# SeniorDesignPCB.net
KiCad netlist of a schematic drawn in Altium Designer
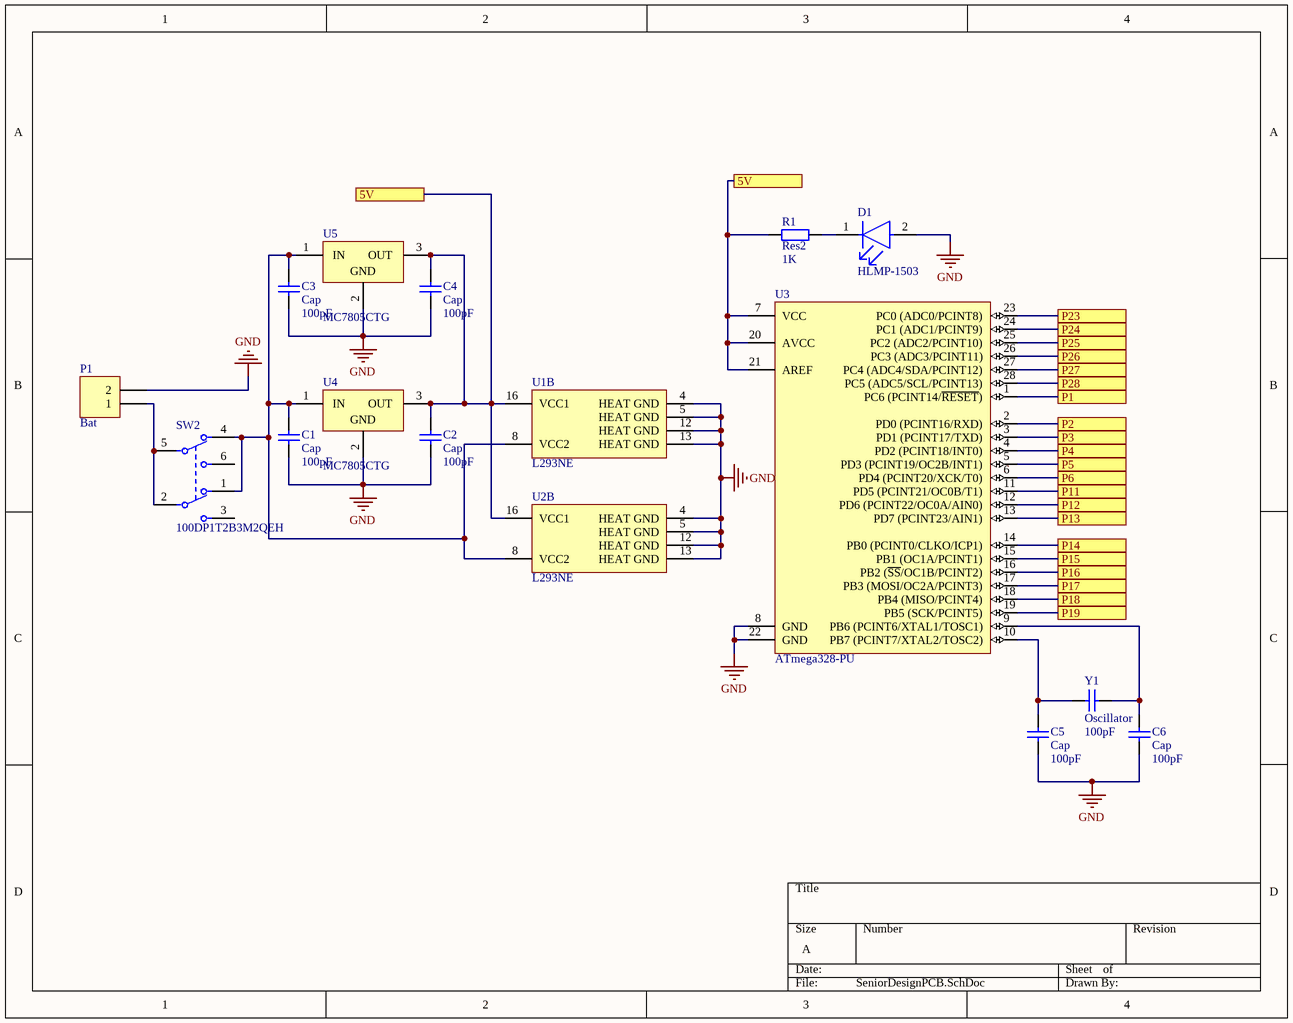
[diagram p0: SeniorDesignPCB.SchDoc]

(export (version "E")
  (design (tool "Eeschema 10.0.6"))
  (components
    (comp (ref "C1")
      (value "Cap")
      (footprint "RAD-0.3")
      (description "Capacitor 10 uF")
      (fields (field (name "ALTIUM_VALUE") "100pF") (field (name "PUBLISHER") "Altium Limited"))
      (libsource (lib "Miscellaneous Devices") (part "Cap"))
    )
    (comp (ref "C2")
      (value "Cap")
      (footprint "RAD-0.3")
      (description "Capacitor 10 uF")
      (fields (field (name "ALTIUM_VALUE") "100pF") (field (name "PUBLISHER") "Altium Limited"))
      (libsource (lib "Miscellaneous Devices") (part "Cap"))
    )
    (comp (ref "C3")
      (value "Cap")
      (footprint "RAD-0.3")
      (description "Capacitor 10 uF")
      (fields (field (name "ALTIUM_VALUE") "100pF") (field (name "PUBLISHER") "Altium Limited"))
      (libsource (lib "Miscellaneous Devices") (part "Cap"))
    )
    (comp (ref "C4")
      (value "Cap")
      (footprint "RAD-0.3")
      (description "Capacitor 10 uF")
      (fields (field (name "ALTIUM_VALUE") "100pF") (field (name "PUBLISHER") "Altium Limited"))
      (libsource (lib "Miscellaneous Devices") (part "Cap"))
    )
    (comp (ref "C5")
      (value "Cap")
      (footprint "RAD-0.3")
      (description "Capacitor 22 pF")
      (fields (field (name "ALTIUM_VALUE") "100pF") (field (name "PUBLISHER") "Altium Limited"))
      (libsource (lib "Miscellaneous Devices") (part "Cap"))
    )
    (comp (ref "C6")
      (value "Cap")
      (footprint "RAD-0.3")
      (description "Capacitor 22 pF")
      (fields (field (name "ALTIUM_VALUE") "100pF") (field (name "PUBLISHER") "Altium Limited"))
      (libsource (lib "Miscellaneous Devices") (part "Cap"))
    )
    (comp (ref "D1")
      (value "HLMP-1503")
      (footprint "FP-HLMP-1503-MFG")
      (description "LED GREEN DIFFUSED T-1 T/H")
      (fields
        (field (name "MANUFACTURER") "Broadcom")
        (field (name "OCTOPART") "https://octopart.com/hlmp-1503-broadcom-71130371")
      )
      (libsource (lib "Altium Content Vault") (part "8706943c75ba83719d021d2fdc84c58"))
    )
    (comp (ref "P1")
      (value "Bat")
      (footprint "HDR1X2")
      (description "Header, 2-Pin")
      (fields (field (name "PUBLISHER") "Altium Limited"))
      (libsource (lib "Miscellaneous Connectors") (part "Header 2"))
    )
    (comp (ref "R1")
      (value "Res2")
      (footprint "AXIAL-0.4")
      (description "Resistor 220 ohm")
      (fields (field (name "ALTIUM_VALUE") "1K") (field (name "PUBLISHER") "Altium Limited"))
      (libsource (lib "Miscellaneous Devices") (part "Res2"))
    )
    (comp (ref "SW2")
      (value "100DP1T2B3M2QEH")
      (footprint "FP-100DP1T2B3M2QEH-MFG")
      (description "DPDT Toggle Switch")
      (fields (field (name "MANUFACTURER") "E-Switch"))
      (libsource (lib "Altium Content Vault") (part "0cfc74b8a78428f8f812a73d8c28120"))
    )
    (comp (ref "U1")
      (value "L293NE")
      (footprint "NE0016A")
      (description "Quadruple Half-H Driver, 4.5 to 36 V, 0 to 70 degC, 16-Pin DIP, Pb-Free, Tube")
      (fields (field (name "MANUFACTURER") "Texas Instruments"))
      (libsource (lib "Altium Content Vault") (part "TI-L293-NE16"))
    )
    (comp (ref "U2")
      (value "L293NE")
      (footprint "NE0016A")
      (description "Quadruple Half-H Driver, 4.5 to 36 V, 0 to 70 degC, 16-Pin DIP, Pb-Free, Tube")
      (fields (field (name "MANUFACTURER") "Texas Instruments"))
      (libsource (lib "Altium Content Vault") (part "TI-L293-NE16"))
    )
    (comp (ref "U3")
      (value "ATmega328-PU")
      (footprint "28P3")
      (libsource (lib "Altium Content Vault") (part "MC-8B-ATM48-IL28"))
    )
    (comp (ref "U4")
      (value "MC7805CTG")
      (footprint "ONSC-TO-220-3-221AB-01")
      (description "Positive Voltage Regulator, 1 A, 5 V, 0 to 125 degC, 3-Pin TO-220, RoHS, Tube")
      (fields (field (name "MANUFACTURER") "ON Semiconductor"))
      (libsource (lib "Altium Content Vault") (part "ONSC-MC7805CTG-TO-220-3"))
    )
    (comp (ref "U5")
      (value "MC7805CTG")
      (footprint "ONSC-TO-220-3-221AB-01")
      (description "Positive Voltage Regulator, 1 A, 5 V, 0 to 125 degC, 3-Pin TO-220, RoHS, Tube")
      (fields (field (name "MANUFACTURER") "ON Semiconductor"))
      (libsource (lib "Altium Content Vault") (part "ONSC-MC7805CTG-TO-220-3"))
    )
    (comp (ref "Y1")
      (value "Oscillator")
      (footprint "RAD-0.3")
      (description "16 MHz oscillator")
      (fields (field (name "ALTIUM_VALUE") "100pF") (field (name "PUBLISHER") "Altium Limited"))
      (libsource (lib "Miscellaneous Devices") (part "Cap"))
    )
  )
  (nets
    (net (code "1") (name "/5V") (class "Default")
      (node (ref "C2") (pin "2") (pinfunction "2_2") (pintype "passive"))
      (node (ref "C4") (pin "2") (pinfunction "2_2") (pintype "passive"))
      (node (ref "R1") (pin "1") (pinfunction "1_1") (pintype "passive"))
      (node (ref "U1") (pin "16") (pinfunction "VCC1_16") (pintype "power_in"))
      (node (ref "U2") (pin "16") (pinfunction "VCC1_16") (pintype "power_in"))
      (node (ref "U3") (pin "20") (pinfunction "AVCC_20") (pintype "power_in"))
      (node (ref "U3") (pin "21") (pinfunction "AREF_21") (pintype "power_in"))
      (node (ref "U3") (pin "7") (pinfunction "VCC_7") (pintype "power_in"))
      (node (ref "U4") (pin "3") (pinfunction "OUT_3") (pintype "power_in"))
      (node (ref "U5") (pin "3") (pinfunction "OUT_3") (pintype "power_in"))
    )
    (net (code "2") (name "/P1") (class "Default")
      (node (ref "U3") (pin "1") (pinfunction "PC6_(PCINT14/~{RESET})_1") (pintype "bidirectional"))
    )
    (net (code "3") (name "/P2") (class "Default")
      (node (ref "U3") (pin "2") (pinfunction "PD0_(PCINT16/RXD)_2") (pintype "bidirectional"))
    )
    (net (code "4") (name "/P3") (class "Default")
      (node (ref "U3") (pin "3") (pinfunction "PD1_(PCINT17/TXD)_3") (pintype "bidirectional"))
    )
    (net (code "5") (name "/P4") (class "Default")
      (node (ref "U3") (pin "4") (pinfunction "PD2_(PCINT18/INT0)_4") (pintype "bidirectional"))
    )
    (net (code "6") (name "/P5") (class "Default")
      (node (ref "U3") (pin "5") (pinfunction "PD3_(PCINT19/OC2B/INT1)_5") (pintype "bidirectional"))
    )
    (net (code "7") (name "/P6") (class "Default")
      (node (ref "U3") (pin "6") (pinfunction "PD4_(PCINT20/XCK/T0)_6") (pintype "bidirectional"))
    )
    (net (code "8") (name "/P11") (class "Default")
      (node (ref "U3") (pin "11") (pinfunction "PD5_(PCINT21/OC0B/T1)_11") (pintype "bidirectional"))
    )
    (net (code "9") (name "/P12") (class "Default")
      (node (ref "U3") (pin "12") (pinfunction "PD6_(PCINT22/OC0A/AIN0)_12") (pintype "bidirectional"))
    )
    (net (code "10") (name "/P13") (class "Default")
      (node (ref "U3") (pin "13") (pinfunction "PD7_(PCINT23/AIN1)_13") (pintype "bidirectional"))
    )
    (net (code "11") (name "/P14") (class "Default")
      (node (ref "U3") (pin "14") (pinfunction "PB0_(PCINT0/CLKO/ICP1)_14") (pintype "bidirectional"))
    )
    (net (code "12") (name "/P15") (class "Default")
      (node (ref "U3") (pin "15") (pinfunction "PB1_(OC1A/PCINT1)_15") (pintype "bidirectional"))
    )
    (net (code "13") (name "/P16") (class "Default")
      (node (ref "U3") (pin "16") (pinfunction "PB2_(~{SS}/OC1B/PCINT2)_16") (pintype "bidirectional"))
    )
    (net (code "14") (name "/P17") (class "Default")
      (node (ref "U3") (pin "17") (pinfunction "PB3_(MOSI/OC2A/PCINT3)_17") (pintype "bidirectional"))
    )
    (net (code "15") (name "/P18") (class "Default")
      (node (ref "U3") (pin "18") (pinfunction "PB4_(MISO/PCINT4)_18") (pintype "bidirectional"))
    )
    (net (code "16") (name "/P19") (class "Default")
      (node (ref "U3") (pin "19") (pinfunction "PB5_(SCK/PCINT5)_19") (pintype "bidirectional"))
    )
    (net (code "17") (name "/P23") (class "Default")
      (node (ref "U3") (pin "23") (pinfunction "PC0_(ADC0/PCINT8)_23") (pintype "bidirectional"))
    )
    (net (code "18") (name "/P24") (class "Default")
      (node (ref "U3") (pin "24") (pinfunction "PC1_(ADC1/PCINT9)_24") (pintype "bidirectional"))
    )
    (net (code "19") (name "/P25") (class "Default")
      (node (ref "U3") (pin "25") (pinfunction "PC2_(ADC2/PCINT10)_25") (pintype "bidirectional"))
    )
    (net (code "20") (name "/P26") (class "Default")
      (node (ref "U3") (pin "26") (pinfunction "PC3_(ADC3/PCINT11)_26") (pintype "bidirectional"))
    )
    (net (code "21") (name "/P27") (class "Default")
      (node (ref "U3") (pin "27") (pinfunction "PC4_(ADC4/SDA/PCINT12)_27") (pintype "bidirectional"))
    )
    (net (code "22") (name "/P28") (class "Default")
      (node (ref "U3") (pin "28") (pinfunction "PC5_(ADC5/SCL/PCINT13)_28") (pintype "bidirectional"))
    )
    (net (code "23") (name "GND") (class "Default")
      (node (ref "C1") (pin "1") (pinfunction "1_1") (pintype "passive"))
      (node (ref "C2") (pin "1") (pinfunction "1_1") (pintype "passive"))
      (node (ref "C3") (pin "1") (pinfunction "1_1") (pintype "passive"))
      (node (ref "C4") (pin "1") (pinfunction "1_1") (pintype "passive"))
      (node (ref "C5") (pin "1") (pinfunction "1_1") (pintype "passive"))
      (node (ref "C6") (pin "1") (pinfunction "1_1") (pintype "passive"))
      (node (ref "D1") (pin "2") (pinfunction "A_2") (pintype "passive"))
      (node (ref "P1") (pin "2") (pinfunction "2_2") (pintype "passive"))
      (node (ref "U1") (pin "12") (pinfunction "HEAT_GND_12") (pintype "power_in"))
      (node (ref "U1") (pin "13") (pinfunction "HEAT_GND_13") (pintype "power_in"))
      (node (ref "U1") (pin "4") (pinfunction "HEAT_GND_4") (pintype "power_in"))
      (node (ref "U1") (pin "5") (pinfunction "HEAT_GND_5") (pintype "power_in"))
      (node (ref "U2") (pin "12") (pinfunction "HEAT_GND_12") (pintype "power_in"))
      (node (ref "U2") (pin "13") (pinfunction "HEAT_GND_13") (pintype "power_in"))
      (node (ref "U2") (pin "4") (pinfunction "HEAT_GND_4") (pintype "power_in"))
      (node (ref "U2") (pin "5") (pinfunction "HEAT_GND_5") (pintype "power_in"))
      (node (ref "U3") (pin "22") (pinfunction "GND_22") (pintype "power_in"))
      (node (ref "U3") (pin "8") (pinfunction "GND_8") (pintype "power_in"))
      (node (ref "U4") (pin "2") (pinfunction "GND_2") (pintype "power_in"))
      (node (ref "U5") (pin "2") (pinfunction "GND_2") (pintype "power_in"))
    )
    (net (code "24") (name "Net-(D1-C)") (class "Default")
      (node (ref "D1") (pin "1") (pinfunction "C_1") (pintype "passive"))
      (node (ref "R1") (pin "2") (pinfunction "2_2") (pintype "passive"))
    )
    (net (code "25") (name "Net-(P1-Pad1)") (class "Default")
      (node (ref "P1") (pin "1") (pinfunction "1_1") (pintype "passive"))
      (node (ref "SW2") (pin "2") (pinfunction "2_2") (pintype "passive"))
      (node (ref "SW2") (pin "5") (pinfunction "5_5") (pintype "passive"))
    )
    (net (code "26") (name "Net-(U1B-VCC2)") (class "Default")
      (node (ref "C1") (pin "2") (pinfunction "2_2") (pintype "passive"))
      (node (ref "C3") (pin "2") (pinfunction "2_2") (pintype "passive"))
      (node (ref "SW2") (pin "1") (pinfunction "1_1") (pintype "passive"))
      (node (ref "SW2") (pin "4") (pinfunction "4_4") (pintype "passive"))
      (node (ref "U1") (pin "8") (pinfunction "VCC2_8") (pintype "power_in"))
      (node (ref "U2") (pin "8") (pinfunction "VCC2_8") (pintype "power_in"))
      (node (ref "U4") (pin "1") (pinfunction "IN_1") (pintype "power_in"))
      (node (ref "U5") (pin "1") (pinfunction "IN_1") (pintype "power_in"))
    )
    (net (code "27") (name "Net-(U3-PB6_(PCINT6{slash}XTAL1{slash}TOSC1))") (class "Default")
      (node (ref "C6") (pin "2") (pinfunction "2_2") (pintype "passive"))
      (node (ref "U3") (pin "9") (pinfunction "PB6_(PCINT6/XTAL1/TOSC1)_9") (pintype "bidirectional"))
      (node (ref "Y1") (pin "1") (pinfunction "1_1") (pintype "passive"))
    )
    (net (code "28") (name "Net-(U3-PB7_(PCINT7{slash}XTAL2{slash}TOSC2))") (class "Default")
      (node (ref "C5") (pin "2") (pinfunction "2_2") (pintype "passive"))
      (node (ref "U3") (pin "10") (pinfunction "PB7_(PCINT7/XTAL2/TOSC2)_10") (pintype "bidirectional"))
      (node (ref "Y1") (pin "2") (pinfunction "2_2") (pintype "passive"))
    )
    (net (code "29") (name "unconnected-(SW2-Pad3)") (class "Default")
      (node (ref "SW2") (pin "3") (pinfunction "3_3") (pintype "passive"))
    )
    (net (code "30") (name "unconnected-(SW2-Pad6)") (class "Default")
      (node (ref "SW2") (pin "6") (pinfunction "6_6") (pintype "passive"))
    )
  )
)
